# 27c322adapter_3_2.net
KiCad netlist of a schematic drawn in EAGLE
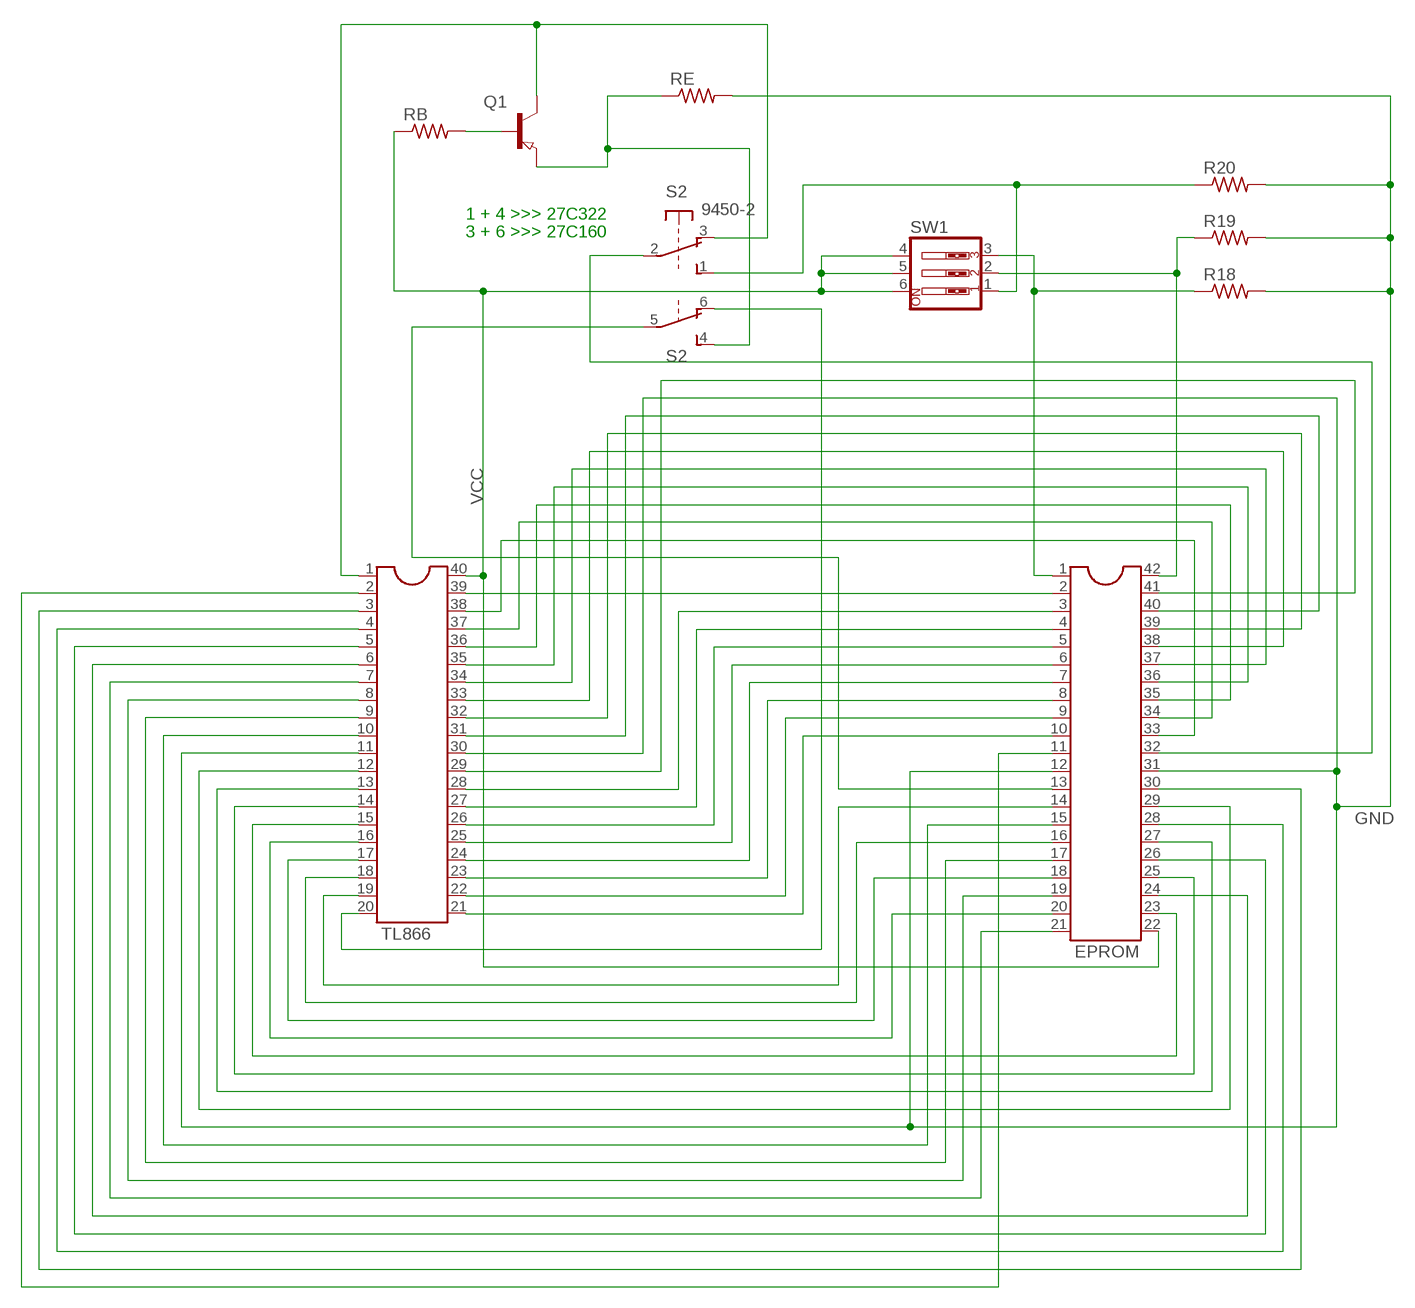
[diagram p0: schematic, sheet 1]

(export (version "E")
  (design (tool "Eeschema 10.0.6"))
  (components
    (comp (ref "IC1")
      (value "EPROM")
      (footprint "eagle-import:DIL42_SLIM")
      (libsource (lib "eagle-import") (part "DIL42_SLIM"))
    )
    (comp (ref "Q1")
      (value "PNP-TRANSISTOR_SOT23")
      (footprint "eagle-import:SOT23")
      (libsource (lib "eagle-import") (part "PNP-TRANSISTOR_SOT23"))
    )
    (comp (ref "R18")
      (value "R-US_R0805")
      (footprint "eagle-import:R0805")
      (libsource (lib "eagle-import") (part "R-US_R0805"))
    )
    (comp (ref "R19")
      (value "R-US_R0805")
      (footprint "eagle-import:R0805")
      (libsource (lib "eagle-import") (part "R-US_R0805"))
    )
    (comp (ref "R20")
      (value "R-US_R0805")
      (footprint "eagle-import:R0805")
      (libsource (lib "eagle-import") (part "R-US_R0805"))
    )
    (comp (ref "RB")
      (value "R-US_R0805")
      (footprint "eagle-import:R0805")
      (libsource (lib "eagle-import") (part "R-US_R0805"))
    )
    (comp (ref "RE")
      (value "R-US_R0805")
      (footprint "eagle-import:R0805")
      (libsource (lib "eagle-import") (part "R-US_R0805"))
    )
    (comp (ref "S2")
      (value "9450-2")
      (footprint "eagle-import:9450-2")
      (libsource (lib "eagle-import") (part "9450-2"))
    )
    (comp (ref "SW1")
      (value "SW_DIP-3")
      (footprint "eagle-import:EDG-03")
      (libsource (lib "eagle-import") (part "SW_DIP-3"))
    )
    (comp (ref "TL866")
      (value "TL866")
      (footprint "eagle-import:DIL40_SLIM")
      (libsource (lib "eagle-import") (part "DIL40_SLIM"))
    )
  )
  (nets
    (net (code "1") (name "/GND") (class "Default")
      (node (ref "IC1") (pin "12") (pinfunction "12_12") (pintype "passive"))
      (node (ref "IC1") (pin "31") (pinfunction "31_31") (pintype "passive"))
      (node (ref "R18") (pin "2") (pinfunction "2_2") (pintype "passive"))
      (node (ref "R19") (pin "2") (pinfunction "2_2") (pintype "passive"))
      (node (ref "R20") (pin "2") (pinfunction "2_2") (pintype "passive"))
      (node (ref "RE") (pin "2") (pinfunction "2_2") (pintype "passive"))
      (node (ref "TL866") (pin "11") (pinfunction "11_11") (pintype "passive"))
      (node (ref "TL866") (pin "30") (pinfunction "30_30") (pintype "passive"))
    )
    (net (code "2") (name "/VCC") (class "Default")
      (node (ref "IC1") (pin "22") (pinfunction "22_22") (pintype "passive"))
      (node (ref "RB") (pin "1") (pinfunction "1_1") (pintype "passive"))
      (node (ref "SW1") (pin "4") (pinfunction "4_4") (pintype "passive"))
      (node (ref "SW1") (pin "5") (pinfunction "5_5") (pintype "passive"))
      (node (ref "SW1") (pin "6") (pinfunction "6_6") (pintype "passive"))
      (node (ref "TL866") (pin "40") (pinfunction "40_40") (pintype "passive"))
    )
    (net (code "3") (name "Net-(IC1-Pad1)") (class "Default")
      (node (ref "IC1") (pin "1") (pinfunction "1_1") (pintype "passive"))
      (node (ref "R18") (pin "1") (pinfunction "1_1") (pintype "passive"))
      (node (ref "SW1") (pin "3") (pinfunction "3_3") (pintype "passive"))
    )
    (net (code "4") (name "Net-(IC1-Pad2)") (class "Default")
      (node (ref "IC1") (pin "2") (pinfunction "2_2") (pintype "passive"))
      (node (ref "TL866") (pin "39") (pinfunction "39_39") (pintype "passive"))
    )
    (net (code "5") (name "Net-(IC1-Pad3)") (class "Default")
      (node (ref "IC1") (pin "3") (pinfunction "3_3") (pintype "passive"))
      (node (ref "TL866") (pin "28") (pinfunction "28_28") (pintype "passive"))
    )
    (net (code "6") (name "Net-(IC1-Pad4)") (class "Default")
      (node (ref "IC1") (pin "4") (pinfunction "4_4") (pintype "passive"))
      (node (ref "TL866") (pin "27") (pinfunction "27_27") (pintype "passive"))
    )
    (net (code "7") (name "Net-(IC1-Pad5)") (class "Default")
      (node (ref "IC1") (pin "5") (pinfunction "5_5") (pintype "passive"))
      (node (ref "TL866") (pin "26") (pinfunction "26_26") (pintype "passive"))
    )
    (net (code "8") (name "Net-(IC1-Pad6)") (class "Default")
      (node (ref "IC1") (pin "6") (pinfunction "6_6") (pintype "passive"))
      (node (ref "TL866") (pin "25") (pinfunction "25_25") (pintype "passive"))
    )
    (net (code "9") (name "Net-(IC1-Pad7)") (class "Default")
      (node (ref "IC1") (pin "7") (pinfunction "7_7") (pintype "passive"))
      (node (ref "TL866") (pin "24") (pinfunction "24_24") (pintype "passive"))
    )
    (net (code "10") (name "Net-(IC1-Pad8)") (class "Default")
      (node (ref "IC1") (pin "8") (pinfunction "8_8") (pintype "passive"))
      (node (ref "TL866") (pin "23") (pinfunction "23_23") (pintype "passive"))
    )
    (net (code "11") (name "Net-(IC1-Pad9)") (class "Default")
      (node (ref "IC1") (pin "9") (pinfunction "9_9") (pintype "passive"))
      (node (ref "TL866") (pin "22") (pinfunction "22_22") (pintype "passive"))
    )
    (net (code "12") (name "Net-(IC1-Pad10)") (class "Default")
      (node (ref "IC1") (pin "10") (pinfunction "10_10") (pintype "passive"))
      (node (ref "TL866") (pin "21") (pinfunction "21_21") (pintype "passive"))
    )
    (net (code "13") (name "Net-(IC1-Pad11)") (class "Default")
      (node (ref "IC1") (pin "11") (pinfunction "11_11") (pintype "passive"))
      (node (ref "TL866") (pin "2") (pinfunction "2_2") (pintype "passive"))
    )
    (net (code "14") (name "Net-(IC1-Pad14)") (class "Default")
      (node (ref "IC1") (pin "14") (pinfunction "14_14") (pintype "passive"))
      (node (ref "TL866") (pin "19") (pinfunction "19_19") (pintype "passive"))
    )
    (net (code "15") (name "Net-(IC1-Pad15)") (class "Default")
      (node (ref "IC1") (pin "15") (pinfunction "15_15") (pintype "passive"))
      (node (ref "TL866") (pin "10") (pinfunction "10_10") (pintype "passive"))
    )
    (net (code "16") (name "Net-(IC1-Pad16)") (class "Default")
      (node (ref "IC1") (pin "16") (pinfunction "16_16") (pintype "passive"))
      (node (ref "TL866") (pin "18") (pinfunction "18_18") (pintype "passive"))
    )
    (net (code "17") (name "Net-(IC1-Pad17)") (class "Default")
      (node (ref "IC1") (pin "17") (pinfunction "17_17") (pintype "passive"))
      (node (ref "TL866") (pin "9") (pinfunction "9_9") (pintype "passive"))
    )
    (net (code "18") (name "Net-(IC1-Pad18)") (class "Default")
      (node (ref "IC1") (pin "18") (pinfunction "18_18") (pintype "passive"))
      (node (ref "TL866") (pin "17") (pinfunction "17_17") (pintype "passive"))
    )
    (net (code "19") (name "Net-(IC1-Pad19)") (class "Default")
      (node (ref "IC1") (pin "19") (pinfunction "19_19") (pintype "passive"))
      (node (ref "TL866") (pin "8") (pinfunction "8_8") (pintype "passive"))
    )
    (net (code "20") (name "Net-(IC1-Pad20)") (class "Default")
      (node (ref "IC1") (pin "20") (pinfunction "20_20") (pintype "passive"))
      (node (ref "TL866") (pin "16") (pinfunction "16_16") (pintype "passive"))
    )
    (net (code "21") (name "Net-(IC1-Pad21)") (class "Default")
      (node (ref "IC1") (pin "21") (pinfunction "21_21") (pintype "passive"))
      (node (ref "TL866") (pin "7") (pinfunction "7_7") (pintype "passive"))
    )
    (net (code "22") (name "Net-(IC1-Pad23)") (class "Default")
      (node (ref "IC1") (pin "23") (pinfunction "23_23") (pintype "passive"))
      (node (ref "TL866") (pin "15") (pinfunction "15_15") (pintype "passive"))
    )
    (net (code "23") (name "Net-(IC1-Pad24)") (class "Default")
      (node (ref "IC1") (pin "24") (pinfunction "24_24") (pintype "passive"))
      (node (ref "TL866") (pin "6") (pinfunction "6_6") (pintype "passive"))
    )
    (net (code "24") (name "Net-(IC1-Pad25)") (class "Default")
      (node (ref "IC1") (pin "25") (pinfunction "25_25") (pintype "passive"))
      (node (ref "TL866") (pin "14") (pinfunction "14_14") (pintype "passive"))
    )
    (net (code "25") (name "Net-(IC1-Pad26)") (class "Default")
      (node (ref "IC1") (pin "26") (pinfunction "26_26") (pintype "passive"))
      (node (ref "TL866") (pin "5") (pinfunction "5_5") (pintype "passive"))
    )
    (net (code "26") (name "Net-(IC1-Pad27)") (class "Default")
      (node (ref "IC1") (pin "27") (pinfunction "27_27") (pintype "passive"))
      (node (ref "TL866") (pin "13") (pinfunction "13_13") (pintype "passive"))
    )
    (net (code "27") (name "Net-(IC1-Pad28)") (class "Default")
      (node (ref "IC1") (pin "28") (pinfunction "28_28") (pintype "passive"))
      (node (ref "TL866") (pin "4") (pinfunction "4_4") (pintype "passive"))
    )
    (net (code "28") (name "Net-(IC1-Pad29)") (class "Default")
      (node (ref "IC1") (pin "29") (pinfunction "29_29") (pintype "passive"))
      (node (ref "TL866") (pin "12") (pinfunction "12_12") (pintype "passive"))
    )
    (net (code "29") (name "Net-(IC1-Pad30)") (class "Default")
      (node (ref "IC1") (pin "30") (pinfunction "30_30") (pintype "passive"))
      (node (ref "TL866") (pin "3") (pinfunction "3_3") (pintype "passive"))
    )
    (net (code "30") (name "Net-(IC1-Pad33)") (class "Default")
      (node (ref "IC1") (pin "33") (pinfunction "33_33") (pintype "passive"))
      (node (ref "TL866") (pin "38") (pinfunction "38_38") (pintype "passive"))
    )
    (net (code "31") (name "Net-(IC1-Pad34)") (class "Default")
      (node (ref "IC1") (pin "34") (pinfunction "34_34") (pintype "passive"))
      (node (ref "TL866") (pin "37") (pinfunction "37_37") (pintype "passive"))
    )
    (net (code "32") (name "Net-(IC1-Pad35)") (class "Default")
      (node (ref "IC1") (pin "35") (pinfunction "35_35") (pintype "passive"))
      (node (ref "TL866") (pin "36") (pinfunction "36_36") (pintype "passive"))
    )
    (net (code "33") (name "Net-(IC1-Pad36)") (class "Default")
      (node (ref "IC1") (pin "36") (pinfunction "36_36") (pintype "passive"))
      (node (ref "TL866") (pin "35") (pinfunction "35_35") (pintype "passive"))
    )
    (net (code "34") (name "Net-(IC1-Pad37)") (class "Default")
      (node (ref "IC1") (pin "37") (pinfunction "37_37") (pintype "passive"))
      (node (ref "TL866") (pin "34") (pinfunction "34_34") (pintype "passive"))
    )
    (net (code "35") (name "Net-(IC1-Pad38)") (class "Default")
      (node (ref "IC1") (pin "38") (pinfunction "38_38") (pintype "passive"))
      (node (ref "TL866") (pin "33") (pinfunction "33_33") (pintype "passive"))
    )
    (net (code "36") (name "Net-(IC1-Pad39)") (class "Default")
      (node (ref "IC1") (pin "39") (pinfunction "39_39") (pintype "passive"))
      (node (ref "TL866") (pin "32") (pinfunction "32_32") (pintype "passive"))
    )
    (net (code "37") (name "Net-(IC1-Pad40)") (class "Default")
      (node (ref "IC1") (pin "40") (pinfunction "40_40") (pintype "passive"))
      (node (ref "TL866") (pin "31") (pinfunction "31_31") (pintype "passive"))
    )
    (net (code "38") (name "Net-(IC1-Pad41)") (class "Default")
      (node (ref "IC1") (pin "41") (pinfunction "41_41") (pintype "passive"))
      (node (ref "TL866") (pin "29") (pinfunction "29_29") (pintype "passive"))
    )
    (net (code "39") (name "Net-(IC1-Pad42)") (class "Default")
      (node (ref "IC1") (pin "42") (pinfunction "42_42") (pintype "passive"))
      (node (ref "R19") (pin "1") (pinfunction "1_1") (pintype "passive"))
      (node (ref "SW1") (pin "2") (pinfunction "2_2") (pintype "passive"))
    )
    (net (code "40") (name "Net-(Q1-B)") (class "Default")
      (node (ref "Q1") (pin "1") (pinfunction "B_1") (pintype "passive"))
      (node (ref "RB") (pin "2") (pinfunction "2_2") (pintype "passive"))
    )
    (net (code "41") (name "Net-(Q1-C)") (class "Default")
      (node (ref "Q1") (pin "3") (pinfunction "C_3") (pintype "passive"))
      (node (ref "S2") (pin "3") (pinfunction "O_3") (pintype "passive"))
      (node (ref "TL866") (pin "1") (pinfunction "1_1") (pintype "passive"))
    )
    (net (code "42") (name "Net-(Q1-E)") (class "Default")
      (node (ref "Q1") (pin "2") (pinfunction "E_2") (pintype "passive"))
      (node (ref "RE") (pin "1") (pinfunction "1_1") (pintype "passive"))
      (node (ref "S2") (pin "4") (pinfunction "S_4") (pintype "passive"))
    )
    (net (code "43") (name "Net-(S2A-P)") (class "Default")
      (node (ref "IC1") (pin "32") (pinfunction "32_32") (pintype "passive"))
      (node (ref "S2") (pin "2") (pinfunction "P_2") (pintype "passive"))
    )
    (net (code "44") (name "Net-(S2A-S)") (class "Default")
      (node (ref "R20") (pin "1") (pinfunction "1_1") (pintype "passive"))
      (node (ref "S2") (pin "1") (pinfunction "S_1") (pintype "passive"))
      (node (ref "SW1") (pin "1") (pinfunction "1_1") (pintype "passive"))
    )
    (net (code "45") (name "Net-(S2B-O)") (class "Default")
      (node (ref "S2") (pin "6") (pinfunction "O_6") (pintype "passive"))
      (node (ref "TL866") (pin "20") (pinfunction "20_20") (pintype "passive"))
    )
    (net (code "46") (name "Net-(S2B-P)") (class "Default")
      (node (ref "IC1") (pin "13") (pinfunction "13_13") (pintype "passive"))
      (node (ref "S2") (pin "5") (pinfunction "P_5") (pintype "passive"))
    )
  )
)
